# DasAltimeter_V0_2.net
KiCad netlist of a schematic drawn in EAGLE
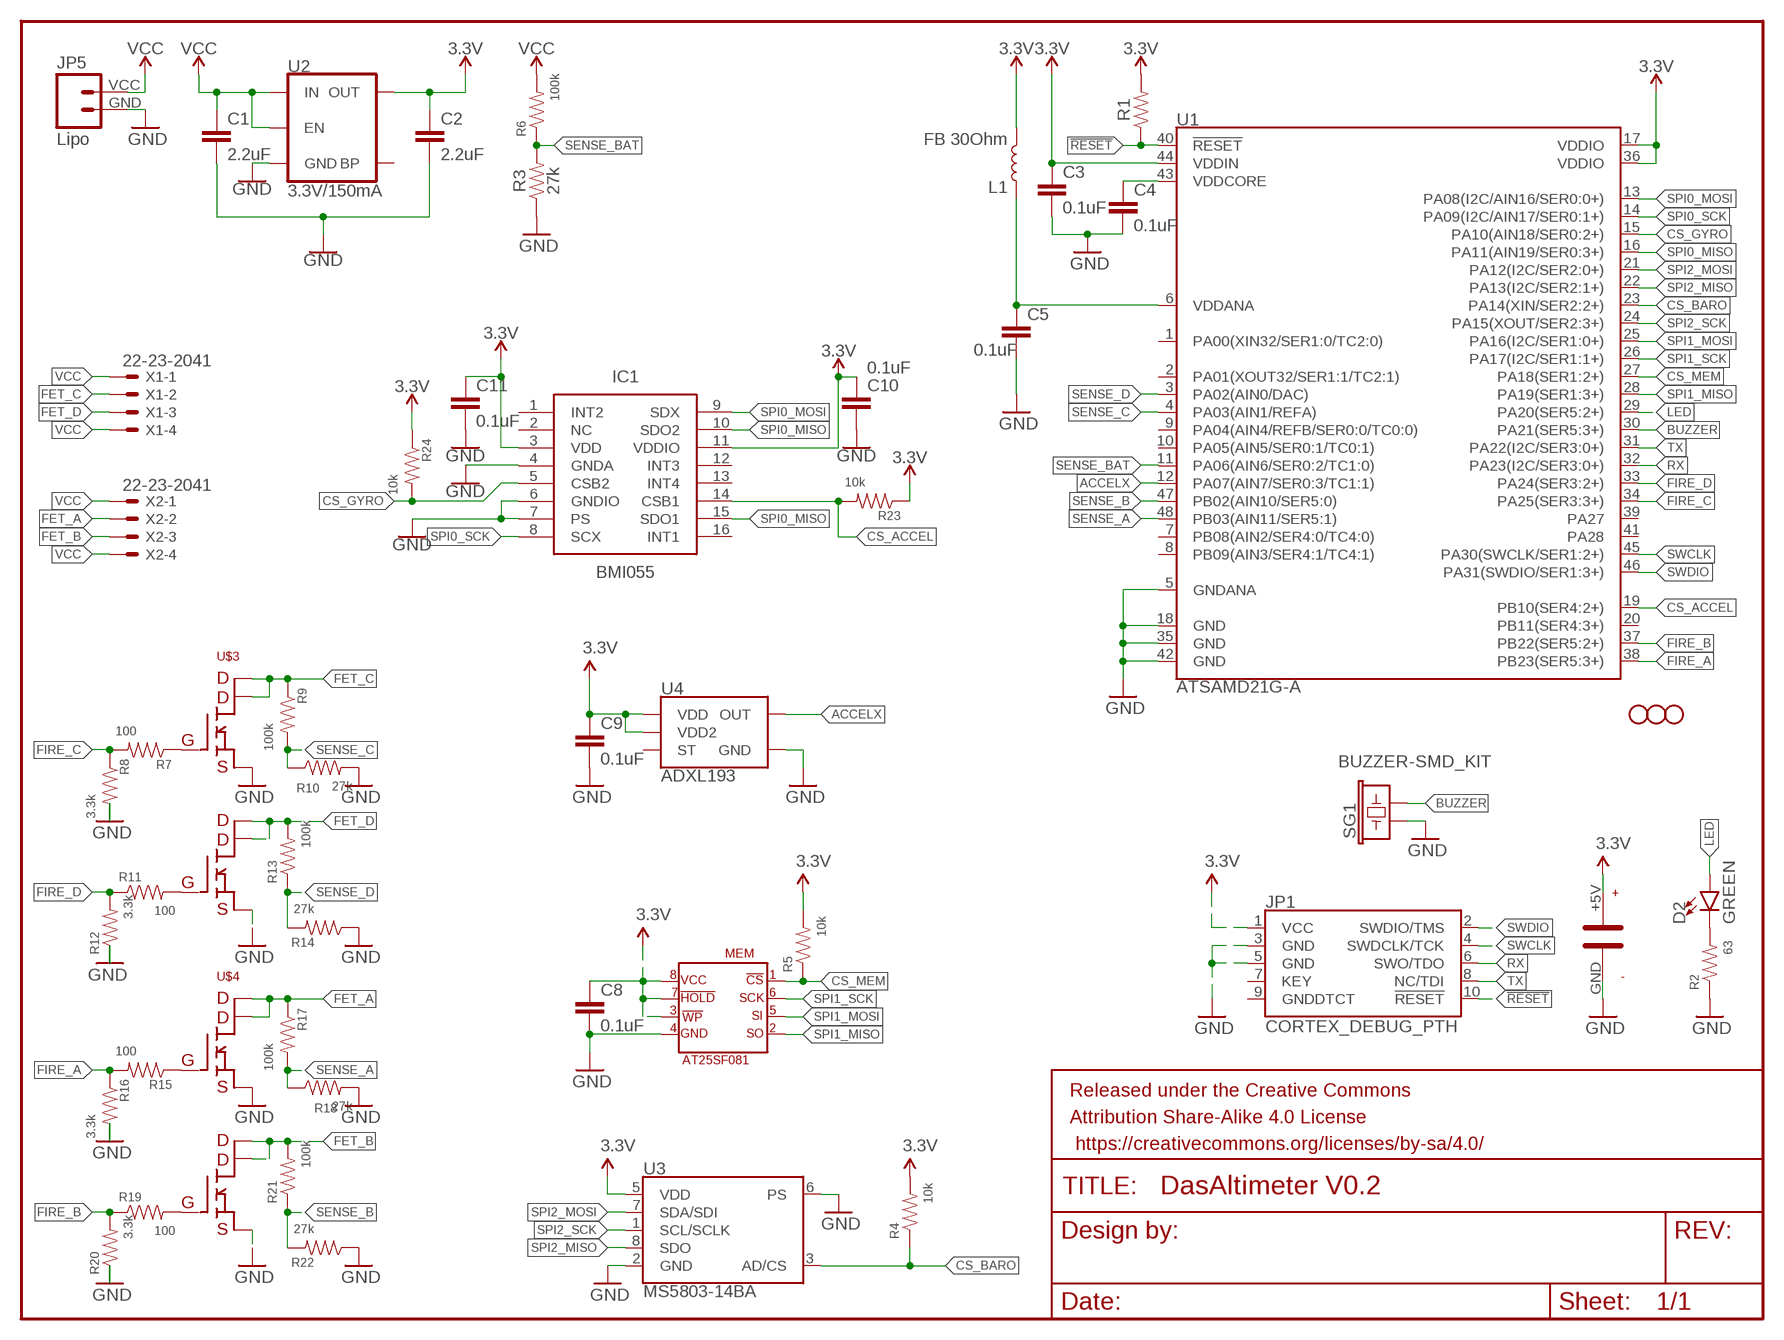
[diagram p0: schematic, sheet 1]

(export (version "E")
  (design (tool "Eeschema 10.0.6"))
  (components
    (comp (ref "C1")
      (value "2.2uF")
      (footprint "eagle-import:0603")
      (libsource (lib "eagle-import") (part "2.2UF-0603-10V-20%"))
    )
    (comp (ref "C2")
      (value "2.2uF")
      (footprint "eagle-import:0603")
      (libsource (lib "eagle-import") (part "2.2UF-0603-10V-20%"))
    )
    (comp (ref "C3")
      (value "0.1uF")
      (footprint "eagle-import:0402")
      (libsource (lib "eagle-import") (part "0.1UF-0402-16V-10%"))
    )
    (comp (ref "C4")
      (value "0.1uF")
      (footprint "eagle-import:0402")
      (libsource (lib "eagle-import") (part "0.1UF-0402-16V-10%"))
    )
    (comp (ref "C5")
      (value "0.1uF")
      (footprint "eagle-import:0402")
      (libsource (lib "eagle-import") (part "0.1UF-0402-16V-10%"))
    )
    (comp (ref "C8")
      (value "0.1uF")
      (footprint "eagle-import:0402")
      (libsource (lib "eagle-import") (part "0.1UF-0402-16V-10%"))
    )
    (comp (ref "C9")
      (value "0.1uF")
      (footprint "eagle-import:0402")
      (libsource (lib "eagle-import") (part "0.1UF-0402-16V-10%"))
    )
    (comp (ref "C10")
      (value "0.1uF")
      (footprint "eagle-import:0402")
      (libsource (lib "eagle-import") (part "0.1UF-0402-16V-10%"))
    )
    (comp (ref "C11")
      (value "0.1uF")
      (footprint "eagle-import:0402")
      (libsource (lib "eagle-import") (part "0.1UF-0402-16V-10%"))
    )
    (comp (ref "D2")
      (value "GREEN")
      (footprint "eagle-import:LED-1206")
      (libsource (lib "eagle-import") (part "LED-GREEN1206"))
    )
    (comp (ref "FRAME1")
      (value "FRAME-LETTERNO_PACKAGE")
      (footprint "eagle-import:DUMMY")
      (fields (field (name "DESIGNER") "Nobody"))
      (libsource (lib "eagle-import") (part "FRAME-LETTERNO_PACKAGE"))
    )
    (comp (ref "H1")
      (value "STAND-OFFTIGHT")
      (footprint "eagle-import:STAND-OFF-TIGHT")
      (libsource (lib "eagle-import") (part "STAND-OFFTIGHT"))
    )
    (comp (ref "H2")
      (value "STAND-OFFTIGHT")
      (footprint "eagle-import:STAND-OFF-TIGHT")
      (libsource (lib "eagle-import") (part "STAND-OFFTIGHT"))
    )
    (comp (ref "H3")
      (value "STAND-OFFTIGHT")
      (footprint "eagle-import:STAND-OFF-TIGHT")
      (libsource (lib "eagle-import") (part "STAND-OFFTIGHT"))
    )
    (comp (ref "IC1")
      (value "BMI055")
      (footprint "eagle-import:BMI055")
      (libsource (lib "eagle-import") (part "BMI055"))
    )
    (comp (ref "JP1")
      (value "CORTEX_DEBUG_PTH")
      (footprint "eagle-import:2X5-PTH-1.27MM")
      (libsource (lib "eagle-import") (part "CORTEX_DEBUG_PTH"))
    )
    (comp (ref "JP5")
      (value "Lipo")
      (footprint "eagle-import:JST-2-SMD-VERT")
      (libsource (lib "eagle-import") (part "M024UCON-15767"))
    )
    (comp (ref "L1")
      (value "FB 30Ohm")
      (footprint "eagle-import:0603")
      (libsource (lib "eagle-import") (part "INDUCTOR-0603-33NH"))
    )
    (comp (ref "MEM")
      (value "AT25SF081")
      (footprint "eagle-import:AT25SF081")
      (libsource (lib "eagle-import") (part "AT25SF081"))
    )
    (comp (ref "R1")
      (value "RESISTOR0402")
      (footprint "eagle-import:0402")
      (libsource (lib "eagle-import") (part "RESISTOR0402"))
    )
    (comp (ref "R2")
      (value "63")
      (footprint "eagle-import:0402")
      (libsource (lib "eagle-import") (part "RESISTOR0402"))
    )
    (comp (ref "R3")
      (value "27k")
      (footprint "eagle-import:0402")
      (libsource (lib "eagle-import") (part "RESISTOR0402"))
    )
    (comp (ref "R4")
      (value "10k")
      (footprint "eagle-import:0402")
      (libsource (lib "eagle-import") (part "RESISTOR0402"))
    )
    (comp (ref "R5")
      (value "10k")
      (footprint "eagle-import:0402")
      (libsource (lib "eagle-import") (part "RESISTOR0402"))
    )
    (comp (ref "R6")
      (value "100k")
      (footprint "eagle-import:0402")
      (libsource (lib "eagle-import") (part "RESISTOR0402"))
    )
    (comp (ref "R7")
      (value "100")
      (footprint "eagle-import:0402")
      (libsource (lib "eagle-import") (part "RESISTOR0402"))
    )
    (comp (ref "R8")
      (value "3.3k")
      (footprint "eagle-import:0402")
      (libsource (lib "eagle-import") (part "RESISTOR0402"))
    )
    (comp (ref "R9")
      (value "100k")
      (footprint "eagle-import:0402")
      (libsource (lib "eagle-import") (part "RESISTOR0402"))
    )
    (comp (ref "R10")
      (value "27k")
      (footprint "eagle-import:0402")
      (libsource (lib "eagle-import") (part "RESISTOR0402"))
    )
    (comp (ref "R11")
      (value "100")
      (footprint "eagle-import:0402")
      (libsource (lib "eagle-import") (part "RESISTOR0402"))
    )
    (comp (ref "R12")
      (value "3.3k")
      (footprint "eagle-import:0402")
      (libsource (lib "eagle-import") (part "RESISTOR0402"))
    )
    (comp (ref "R13")
      (value "100k")
      (footprint "eagle-import:0402")
      (libsource (lib "eagle-import") (part "RESISTOR0402"))
    )
    (comp (ref "R14")
      (value "27k")
      (footprint "eagle-import:0402")
      (libsource (lib "eagle-import") (part "RESISTOR0402"))
    )
    (comp (ref "R15")
      (value "100")
      (footprint "eagle-import:0402")
      (libsource (lib "eagle-import") (part "RESISTOR0402"))
    )
    (comp (ref "R16")
      (value "3.3k")
      (footprint "eagle-import:0402")
      (libsource (lib "eagle-import") (part "RESISTOR0402"))
    )
    (comp (ref "R17")
      (value "100k")
      (footprint "eagle-import:0402")
      (libsource (lib "eagle-import") (part "RESISTOR0402"))
    )
    (comp (ref "R18")
      (value "27k")
      (footprint "eagle-import:0402")
      (libsource (lib "eagle-import") (part "RESISTOR0402"))
    )
    (comp (ref "R19")
      (value "100")
      (footprint "eagle-import:0402")
      (libsource (lib "eagle-import") (part "RESISTOR0402"))
    )
    (comp (ref "R20")
      (value "3.3k")
      (footprint "eagle-import:0402")
      (libsource (lib "eagle-import") (part "RESISTOR0402"))
    )
    (comp (ref "R21")
      (value "100k")
      (footprint "eagle-import:0402")
      (libsource (lib "eagle-import") (part "RESISTOR0402"))
    )
    (comp (ref "R22")
      (value "27k")
      (footprint "eagle-import:0402")
      (libsource (lib "eagle-import") (part "RESISTOR0402"))
    )
    (comp (ref "R23")
      (value "10k")
      (footprint "eagle-import:0402")
      (libsource (lib "eagle-import") (part "RESISTOR0402"))
    )
    (comp (ref "R24")
      (value "10k")
      (footprint "eagle-import:0402")
      (libsource (lib "eagle-import") (part "RESISTOR0402"))
    )
    (comp (ref "SG1")
      (value "BUZZER-SMD_KIT")
      (footprint "eagle-import:BUZZER-CCV-KIT")
      (libsource (lib "eagle-import") (part "BUZZER-SMD_KIT"))
    )
    (comp (ref "U$1")
      (value "PB-5R0H104-R")
      (footprint "eagle-import:PB-5R0H104-R")
      (libsource (lib "eagle-import") (part "PB-5R0H104-R"))
    )
    (comp (ref "U$3")
      (value "SI7232DN")
      (footprint "eagle-import:SI7232DN")
      (libsource (lib "eagle-import") (part "SI7232DN"))
    )
    (comp (ref "U$4")
      (value "SI7232DN")
      (footprint "eagle-import:SI7232DN")
      (libsource (lib "eagle-import") (part "SI7232DN"))
    )
    (comp (ref "U1")
      (value "ATSAMD21G-A")
      (footprint "eagle-import:TQFP-48")
      (libsource (lib "eagle-import") (part "ATSAMD21G-A"))
    )
    (comp (ref "U2")
      (value "3.3V/150mA")
      (footprint "eagle-import:SOT23-5")
      (libsource (lib "eagle-import") (part "V_REG_MIC52053.3V"))
    )
    (comp (ref "U3")
      (value "MS5803-14BA")
      (footprint "eagle-import:MS5803")
      (libsource (lib "eagle-import") (part "MS5803-14BA"))
    )
    (comp (ref "U4")
      (value "ADXL193")
      (footprint "eagle-import:LCC-8")
      (libsource (lib "eagle-import") (part "ADXL193"))
    )
    (comp (ref "X1")
      (value "22-23-2041")
      (footprint "eagle-import:22-23-2041")
      (fields (field (name "MF") "MOLEX"))
      (libsource (lib "eagle-import") (part "22-23-2041"))
    )
    (comp (ref "X2")
      (value "22-23-2041")
      (footprint "eagle-import:22-23-2041")
      (fields (field (name "MF") "MOLEX"))
      (libsource (lib "eagle-import") (part "22-23-2041"))
    )
  )
  (nets
    (net (code "1") (name "/~{RESET}") (class "Default")
      (node (ref "JP1") (pin "10") (pinfunction "~{RESET}_10") (pintype "bidirectional"))
      (node (ref "R1") (pin "1") (pinfunction "1_1") (pintype "passive"))
      (node (ref "U1") (pin "40") (pinfunction "~{RESET}_40") (pintype "bidirectional"))
    )
    (net (code "2") (name "3.3V") (class "Default")
      (node (ref "C10") (pin "1") (pinfunction "1_1") (pintype "passive"))
      (node (ref "C11") (pin "1") (pinfunction "1_1") (pintype "passive"))
      (node (ref "C2") (pin "1") (pinfunction "1_1") (pintype "passive"))
      (node (ref "C3") (pin "1") (pinfunction "1_1") (pintype "passive"))
      (node (ref "C8") (pin "1") (pinfunction "1_1") (pintype "passive"))
      (node (ref "C9") (pin "1") (pinfunction "1_1") (pintype "passive"))
      (node (ref "IC1") (pin "11") (pinfunction "VDDIO_11") (pintype "passive"))
      (node (ref "IC1") (pin "3") (pinfunction "VDD_3") (pintype "passive"))
      (node (ref "JP1") (pin "1") (pinfunction "VCC_1") (pintype "bidirectional"))
      (node (ref "L1") (pin "2") (pinfunction "2_2") (pintype "passive"))
      (node (ref "MEM") (pin "!HOLD") (pinfunction "~{HOLD}_!HOLD") (pintype "bidirectional"))
      (node (ref "MEM") (pin "!WP") (pinfunction "~{WP}_!WP") (pintype "bidirectional"))
      (node (ref "MEM") (pin "VCC") (pinfunction "VCC_VCC") (pintype "bidirectional"))
      (node (ref "R1") (pin "2") (pinfunction "2_2") (pintype "passive"))
      (node (ref "R23") (pin "1") (pinfunction "1_1") (pintype "passive"))
      (node (ref "R24") (pin "1") (pinfunction "1_1") (pintype "passive"))
      (node (ref "R4") (pin "2") (pinfunction "2_2") (pintype "passive"))
      (node (ref "R5") (pin "2") (pinfunction "2_2") (pintype "passive"))
      (node (ref "U$1") (pin "+5V") (pinfunction "+5V_+5V") (pintype "bidirectional"))
      (node (ref "U1") (pin "17") (pinfunction "VDDIO_17") (pintype "bidirectional"))
      (node (ref "U1") (pin "36") (pinfunction "VDDIO_36") (pintype "bidirectional"))
      (node (ref "U1") (pin "44") (pinfunction "VDDIN_44") (pintype "bidirectional"))
      (node (ref "U2") (pin "5") (pinfunction "OUT_5") (pintype "passive"))
      (node (ref "U3") (pin "5") (pinfunction "VDD_5") (pintype "bidirectional"))
      (node (ref "U4") (pin "P$7") (pinfunction "VDD_P$7") (pintype "bidirectional"))
      (node (ref "U4") (pin "P$8") (pinfunction "VDD2_P$8") (pintype "bidirectional"))
    )
    (net (code "3") (name "ACCELX") (class "Default")
      (node (ref "U1") (pin "12") (pinfunction "PA07(AIN7/SER0:3/TC1:1)_12") (pintype "bidirectional"))
      (node (ref "U4") (pin "P$6") (pinfunction "OUT_P$6") (pintype "bidirectional"))
    )
    (net (code "4") (name "BUZZER") (class "Default")
      (node (ref "SG1") (pin "-") (pinfunction "2_-") (pintype "passive"))
      (node (ref "U1") (pin "30") (pinfunction "PA21(SER5:3+)_30") (pintype "bidirectional"))
    )
    (net (code "5") (name "CS_ACCEL") (class "Default")
      (node (ref "IC1") (pin "14") (pinfunction "CSB1_14") (pintype "passive"))
      (node (ref "R23") (pin "2") (pinfunction "2_2") (pintype "passive"))
      (node (ref "U1") (pin "19") (pinfunction "PB10(SER4:2+)_19") (pintype "bidirectional"))
    )
    (net (code "6") (name "CS_BARO") (class "Default")
      (node (ref "R4") (pin "1") (pinfunction "1_1") (pintype "passive"))
      (node (ref "U1") (pin "23") (pinfunction "PA14(XIN/SER2:2+)_23") (pintype "bidirectional"))
      (node (ref "U3") (pin "3") (pinfunction "AD/CS_3") (pintype "bidirectional"))
    )
    (net (code "7") (name "CS_GYRO") (class "Default")
      (node (ref "IC1") (pin "5") (pinfunction "CSB2_5") (pintype "passive"))
      (node (ref "R24") (pin "2") (pinfunction "2_2") (pintype "passive"))
      (node (ref "U1") (pin "15") (pinfunction "PA10(AIN18/SER0:2+)_15") (pintype "bidirectional"))
    )
    (net (code "8") (name "CS_MEM") (class "Default")
      (node (ref "MEM") (pin "!CS") (pinfunction "~{CS}_!CS") (pintype "bidirectional"))
      (node (ref "R5") (pin "1") (pinfunction "1_1") (pintype "passive"))
      (node (ref "U1") (pin "27") (pinfunction "PA18(SER1:2+)_27") (pintype "bidirectional"))
    )
    (net (code "9") (name "FET_A") (class "Default")
      (node (ref "R17") (pin "1") (pinfunction "1_1") (pintype "passive"))
      (node (ref "U$4") (pin "7") (pinfunction "PIN7_7") (pintype "bidirectional"))
      (node (ref "U$4") (pin "8") (pinfunction "PIN8_8") (pintype "bidirectional"))
      (node (ref "U$4") (pin "9") (pinfunction "PIN8_9") (pintype "bidirectional"))
      (node (ref "X2") (pin "2") (pinfunction "S_2") (pintype "passive"))
    )
    (net (code "10") (name "FET_B") (class "Default")
      (node (ref "R21") (pin "2") (pinfunction "2_2") (pintype "passive"))
      (node (ref "U$4") (pin "10") (pinfunction "PIN5_10") (pintype "bidirectional"))
      (node (ref "U$4") (pin "5") (pinfunction "PIN5_5") (pintype "bidirectional"))
      (node (ref "U$4") (pin "6") (pinfunction "PIN6_6") (pintype "bidirectional"))
      (node (ref "X2") (pin "3") (pinfunction "S_3") (pintype "passive"))
    )
    (net (code "11") (name "FET_C") (class "Default")
      (node (ref "R9") (pin "1") (pinfunction "1_1") (pintype "passive"))
      (node (ref "U$3") (pin "7") (pinfunction "PIN7_7") (pintype "bidirectional"))
      (node (ref "U$3") (pin "8") (pinfunction "PIN8_8") (pintype "bidirectional"))
      (node (ref "U$3") (pin "9") (pinfunction "PIN8_9") (pintype "bidirectional"))
      (node (ref "X1") (pin "2") (pinfunction "S_2") (pintype "passive"))
    )
    (net (code "12") (name "FET_D") (class "Default")
      (node (ref "R13") (pin "2") (pinfunction "2_2") (pintype "passive"))
      (node (ref "U$3") (pin "10") (pinfunction "PIN5_10") (pintype "bidirectional"))
      (node (ref "U$3") (pin "5") (pinfunction "PIN5_5") (pintype "bidirectional"))
      (node (ref "U$3") (pin "6") (pinfunction "PIN6_6") (pintype "bidirectional"))
      (node (ref "X1") (pin "3") (pinfunction "S_3") (pintype "passive"))
    )
    (net (code "13") (name "FIRE_A") (class "Default")
      (node (ref "R15") (pin "2") (pinfunction "2_2") (pintype "passive"))
      (node (ref "R16") (pin "1") (pinfunction "1_1") (pintype "passive"))
      (node (ref "U1") (pin "38") (pinfunction "PB23(SER5:3+)_38") (pintype "bidirectional"))
    )
    (net (code "14") (name "FIRE_B") (class "Default")
      (node (ref "R19") (pin "1") (pinfunction "1_1") (pintype "passive"))
      (node (ref "R20") (pin "2") (pinfunction "2_2") (pintype "passive"))
      (node (ref "U1") (pin "37") (pinfunction "PB22(SER5:2+)_37") (pintype "bidirectional"))
    )
    (net (code "15") (name "FIRE_C") (class "Default")
      (node (ref "R7") (pin "2") (pinfunction "2_2") (pintype "passive"))
      (node (ref "R8") (pin "1") (pinfunction "1_1") (pintype "passive"))
      (node (ref "U1") (pin "34") (pinfunction "PA25(SER3:3+)_34") (pintype "bidirectional"))
    )
    (net (code "16") (name "FIRE_D") (class "Default")
      (node (ref "R11") (pin "1") (pinfunction "1_1") (pintype "passive"))
      (node (ref "R12") (pin "2") (pinfunction "2_2") (pintype "passive"))
      (node (ref "U1") (pin "33") (pinfunction "PA24(SER3:2+)_33") (pintype "bidirectional"))
    )
    (net (code "17") (name "GND") (class "Default")
      (node (ref "C1") (pin "2") (pinfunction "2_2") (pintype "passive"))
      (node (ref "C10") (pin "2") (pinfunction "2_2") (pintype "passive"))
      (node (ref "C11") (pin "2") (pinfunction "2_2") (pintype "passive"))
      (node (ref "C2") (pin "2") (pinfunction "2_2") (pintype "passive"))
      (node (ref "C3") (pin "2") (pinfunction "2_2") (pintype "passive"))
      (node (ref "C4") (pin "2") (pinfunction "2_2") (pintype "passive"))
      (node (ref "C5") (pin "2") (pinfunction "2_2") (pintype "passive"))
      (node (ref "C8") (pin "2") (pinfunction "2_2") (pintype "passive"))
      (node (ref "C9") (pin "2") (pinfunction "2_2") (pintype "passive"))
      (node (ref "IC1") (pin "4") (pinfunction "GNDA_4") (pintype "passive"))
      (node (ref "IC1") (pin "6") (pinfunction "GNDIO_6") (pintype "passive"))
      (node (ref "IC1") (pin "7") (pinfunction "PS_7") (pintype "passive"))
      (node (ref "JP1") (pin "3") (pinfunction "GND_3") (pintype "bidirectional"))
      (node (ref "JP1") (pin "5") (pinfunction "GND_5") (pintype "bidirectional"))
      (node (ref "JP5") (pin "GND") (pinfunction "1_GND") (pintype "passive"))
      (node (ref "MEM") (pin "GND") (pinfunction "GND_GND") (pintype "bidirectional"))
      (node (ref "R10") (pin "2") (pinfunction "2_2") (pintype "passive"))
      (node (ref "R12") (pin "1") (pinfunction "1_1") (pintype "passive"))
      (node (ref "R14") (pin "1") (pinfunction "1_1") (pintype "passive"))
      (node (ref "R16") (pin "2") (pinfunction "2_2") (pintype "passive"))
      (node (ref "R18") (pin "2") (pinfunction "2_2") (pintype "passive"))
      (node (ref "R2") (pin "1") (pinfunction "1_1") (pintype "passive"))
      (node (ref "R20") (pin "1") (pinfunction "1_1") (pintype "passive"))
      (node (ref "R22") (pin "1") (pinfunction "1_1") (pintype "passive"))
      (node (ref "R3") (pin "1") (pinfunction "1_1") (pintype "passive"))
      (node (ref "R8") (pin "2") (pinfunction "2_2") (pintype "passive"))
      (node (ref "SG1") (pin "+") (pinfunction "1_+") (pintype "passive"))
      (node (ref "U$1") (pin "GND") (pinfunction "GND_GND") (pintype "bidirectional"))
      (node (ref "U$3") (pin "1") (pinfunction "PIN1_1") (pintype "bidirectional"))
      (node (ref "U$3") (pin "3") (pinfunction "PIN3_3") (pintype "bidirectional"))
      (node (ref "U$4") (pin "1") (pinfunction "PIN1_1") (pintype "bidirectional"))
      (node (ref "U$4") (pin "3") (pinfunction "PIN3_3") (pintype "bidirectional"))
      (node (ref "U1") (pin "18") (pinfunction "GND_18") (pintype "bidirectional"))
      (node (ref "U1") (pin "35") (pinfunction "GND_35") (pintype "bidirectional"))
      (node (ref "U1") (pin "42") (pinfunction "GND_42") (pintype "bidirectional"))
      (node (ref "U1") (pin "5") (pinfunction "GNDANA_5") (pintype "bidirectional"))
      (node (ref "U2") (pin "2") (pinfunction "GND_2") (pintype "input"))
      (node (ref "U3") (pin "2") (pinfunction "GND_2") (pintype "bidirectional"))
      (node (ref "U3") (pin "6") (pinfunction "PS_6") (pintype "bidirectional"))
      (node (ref "U4") (pin "P$3") (pinfunction "GND_P$3") (pintype "bidirectional"))
    )
    (net (code "18") (name "LED") (class "Default")
      (node (ref "D2") (pin "A") (pinfunction "A_A") (pintype "passive"))
      (node (ref "U1") (pin "29") (pinfunction "PA20(SER5:2+)_29") (pintype "bidirectional"))
    )
    (net (code "19") (name "Net-(D2-PadC)") (class "Default")
      (node (ref "D2") (pin "C") (pinfunction "C_C") (pintype "passive"))
      (node (ref "R2") (pin "2") (pinfunction "2_2") (pintype "passive"))
    )
    (net (code "20") (name "Net-(U$3-PIN2)") (class "Default")
      (node (ref "R7") (pin "1") (pinfunction "1_1") (pintype "passive"))
      (node (ref "U$3") (pin "2") (pinfunction "PIN2_2") (pintype "bidirectional"))
    )
    (net (code "21") (name "Net-(U$3-PIN4)") (class "Default")
      (node (ref "R11") (pin "2") (pinfunction "2_2") (pintype "passive"))
      (node (ref "U$3") (pin "4") (pinfunction "PIN4_4") (pintype "bidirectional"))
    )
    (net (code "22") (name "Net-(U$4-PIN2)") (class "Default")
      (node (ref "R15") (pin "1") (pinfunction "1_1") (pintype "passive"))
      (node (ref "U$4") (pin "2") (pinfunction "PIN2_2") (pintype "bidirectional"))
    )
    (net (code "23") (name "Net-(U$4-PIN4)") (class "Default")
      (node (ref "R19") (pin "2") (pinfunction "2_2") (pintype "passive"))
      (node (ref "U$4") (pin "4") (pinfunction "PIN4_4") (pintype "bidirectional"))
    )
    (net (code "24") (name "Net-(U1-VDDANA)") (class "Default")
      (node (ref "C5") (pin "1") (pinfunction "1_1") (pintype "passive"))
      (node (ref "L1") (pin "1") (pinfunction "1_1") (pintype "passive"))
      (node (ref "U1") (pin "6") (pinfunction "VDDANA_6") (pintype "bidirectional"))
    )
    (net (code "25") (name "Net-(U1-VDDCORE)") (class "Default")
      (node (ref "C4") (pin "1") (pinfunction "1_1") (pintype "passive"))
      (node (ref "U1") (pin "43") (pinfunction "VDDCORE_43") (pintype "bidirectional"))
    )
    (net (code "26") (name "RX") (class "Default")
      (node (ref "JP1") (pin "6") (pinfunction "SWO/TDO_6") (pintype "bidirectional"))
      (node (ref "U1") (pin "32") (pinfunction "PA23(I2C/SER3:0+)_32") (pintype "bidirectional"))
    )
    (net (code "27") (name "SENSE_A") (class "Default")
      (node (ref "R17") (pin "2") (pinfunction "2_2") (pintype "passive"))
      (node (ref "R18") (pin "1") (pinfunction "1_1") (pintype "passive"))
      (node (ref "U1") (pin "48") (pinfunction "PB03(AIN11/SER5:1)_48") (pintype "bidirectional"))
    )
    (net (code "28") (name "SENSE_B") (class "Default")
      (node (ref "R21") (pin "1") (pinfunction "1_1") (pintype "passive"))
      (node (ref "R22") (pin "2") (pinfunction "2_2") (pintype "passive"))
      (node (ref "U1") (pin "47") (pinfunction "PB02(AIN10/SER5:0)_47") (pintype "bidirectional"))
    )
    (net (code "29") (name "SENSE_BAT") (class "Default")
      (node (ref "R3") (pin "2") (pinfunction "2_2") (pintype "passive"))
      (node (ref "R6") (pin "1") (pinfunction "1_1") (pintype "passive"))
      (node (ref "U1") (pin "11") (pinfunction "PA06(AIN6/SER0:2/TC1:0)_11") (pintype "bidirectional"))
    )
    (net (code "30") (name "SENSE_C") (class "Default")
      (node (ref "R10") (pin "1") (pinfunction "1_1") (pintype "passive"))
      (node (ref "R9") (pin "2") (pinfunction "2_2") (pintype "passive"))
      (node (ref "U1") (pin "4") (pinfunction "PA03(AIN1/REFA)_4") (pintype "bidirectional"))
    )
    (net (code "31") (name "SENSE_D") (class "Default")
      (node (ref "R13") (pin "1") (pinfunction "1_1") (pintype "passive"))
      (node (ref "R14") (pin "2") (pinfunction "2_2") (pintype "passive"))
      (node (ref "U1") (pin "3") (pinfunction "PA02(AIN0/DAC)_3") (pintype "bidirectional"))
    )
    (net (code "32") (name "SPI0_MISO") (class "Default")
      (node (ref "IC1") (pin "10") (pinfunction "SDO2_10") (pintype "passive"))
      (node (ref "IC1") (pin "15") (pinfunction "SDO1_15") (pintype "passive"))
      (node (ref "U1") (pin "16") (pinfunction "PA11(AIN19/SER0:3+)_16") (pintype "bidirectional"))
    )
    (net (code "33") (name "SPI0_MOSI") (class "Default")
      (node (ref "IC1") (pin "9") (pinfunction "SDX_9") (pintype "passive"))
      (node (ref "U1") (pin "13") (pinfunction "PA08(I2C/AIN16/SER0:0+)_13") (pintype "bidirectional"))
    )
    (net (code "34") (name "SPI0_SCK") (class "Default")
      (node (ref "IC1") (pin "8") (pinfunction "SCX_8") (pintype "passive"))
      (node (ref "U1") (pin "14") (pinfunction "PA09(I2C/AIN17/SER0:1+)_14") (pintype "bidirectional"))
    )
    (net (code "35") (name "SPI1_MISO") (class "Default")
      (node (ref "MEM") (pin "SO") (pinfunction "SO_SO") (pintype "bidirectional"))
      (node (ref "U1") (pin "28") (pinfunction "PA19(SER1:3+)_28") (pintype "bidirectional"))
    )
    (net (code "36") (name "SPI1_MOSI") (class "Default")
      (node (ref "MEM") (pin "SI") (pinfunction "SI_SI") (pintype "bidirectional"))
      (node (ref "U1") (pin "25") (pinfunction "PA16(I2C/SER1:0+)_25") (pintype "bidirectional"))
    )
    (net (code "37") (name "SPI1_SCK") (class "Default")
      (node (ref "MEM") (pin "SCK") (pinfunction "SCK_SCK") (pintype "bidirectional"))
      (node (ref "U1") (pin "26") (pinfunction "PA17(I2C/SER1:1+)_26") (pintype "bidirectional"))
    )
    (net (code "38") (name "SPI2_MISO") (class "Default")
      (node (ref "U1") (pin "22") (pinfunction "PA13(I2C/SER2:1+)_22") (pintype "bidirectional"))
      (node (ref "U3") (pin "8") (pinfunction "SDO_8") (pintype "bidirectional"))
    )
    (net (code "39") (name "SPI2_MOSI") (class "Default")
      (node (ref "U1") (pin "21") (pinfunction "PA12(I2C/SER2:0+)_21") (pintype "bidirectional"))
      (node (ref "U3") (pin "7") (pinfunction "SDA/SDI_7") (pintype "bidirectional"))
    )
    (net (code "40") (name "SPI2_SCK") (class "Default")
      (node (ref "U1") (pin "24") (pinfunction "PA15(XOUT/SER2:3+)_24") (pintype "bidirectional"))
      (node (ref "U3") (pin "1") (pinfunction "SCL/SCLK_1") (pintype "bidirectional"))
    )
    (net (code "41") (name "SWCLK") (class "Default")
      (node (ref "JP1") (pin "4") (pinfunction "SWDCLK/TCK_4") (pintype "bidirectional"))
      (node (ref "U1") (pin "45") (pinfunction "PA30(SWCLK/SER1:2+)_45") (pintype "bidirectional"))
    )
    (net (code "42") (name "SWDIO") (class "Default")
      (node (ref "JP1") (pin "2") (pinfunction "SWDIO/TMS_2") (pintype "bidirectional"))
      (node (ref "U1") (pin "46") (pinfunction "PA31(SWDIO/SER1:3+)_46") (pintype "bidirectional"))
    )
    (net (code "43") (name "TX") (class "Default")
      (node (ref "JP1") (pin "8") (pinfunction "NC/TDI_8") (pintype "bidirectional"))
      (node (ref "U1") (pin "31") (pinfunction "PA22(I2C/SER3:0+)_31") (pintype "bidirectional"))
    )
    (net (code "44") (name "VCC") (class "Default")
      (node (ref "C1") (pin "1") (pinfunction "1_1") (pintype "passive"))
      (node (ref "JP5") (pin "VCC") (pinfunction "2_VCC") (pintype "passive"))
      (node (ref "R6") (pin "2") (pinfunction "2_2") (pintype "passive"))
      (node (ref "U2") (pin "1") (pinfunction "IN_1") (pintype "input"))
      (node (ref "U2") (pin "3") (pinfunction "EN_3") (pintype "input"))
      (node (ref "X1") (pin "1") (pinfunction "S_1") (pintype "passive"))
      (node (ref "X1") (pin "4") (pinfunction "S_4") (pintype "passive"))
      (node (ref "X2") (pin "1") (pinfunction "S_1") (pintype "passive"))
      (node (ref "X2") (pin "4") (pinfunction "S_4") (pintype "passive"))
    )
    (net (code "45") (name "unconnected-(IC1-INT1-Pad16)") (class "Default")
      (node (ref "IC1") (pin "16") (pinfunction "INT1_16") (pintype "passive"))
    )
    (net (code "46") (name "unconnected-(IC1-INT2-Pad1)") (class "Default")
      (node (ref "IC1") (pin "1") (pinfunction "INT2_1") (pintype "passive"))
    )
    (net (code "47") (name "unconnected-(IC1-INT3-Pad12)") (class "Default")
      (node (ref "IC1") (pin "12") (pinfunction "INT3_12") (pintype "passive"))
    )
    (net (code "48") (name "unconnected-(IC1-INT4-Pad13)") (class "Default")
      (node (ref "IC1") (pin "13") (pinfunction "INT4_13") (pintype "passive"))
    )
    (net (code "49") (name "unconnected-(IC1-NC-Pad2)") (class "Default")
      (node (ref "IC1") (pin "2") (pinfunction "NC_2") (pintype "no_connect"))
    )
    (net (code "50") (name "unconnected-(JP1-GNDDTCT-Pad9)") (class "Default")
      (node (ref "JP1") (pin "9") (pinfunction "GNDDTCT_9") (pintype "bidirectional"))
    )
    (net (code "51") (name "unconnected-(JP1-KEY-Pad7)") (class "Default")
      (node (ref "JP1") (pin "7") (pinfunction "KEY_7") (pintype "bidirectional"))
    )
    (net (code "52") (name "unconnected-(U1-PA00(XIN32{slash}SER1:0{slash}TC2:0)-Pad1)") (class "Default")
      (node (ref "U1") (pin "1") (pinfunction "PA00(XIN32/SER1:0/TC2:0)_1") (pintype "bidirectional"))
    )
    (net (code "53") (name "unconnected-(U1-PA01(XOUT32{slash}SER1:1{slash}TC2:1)-Pad2)") (class "Default")
      (node (ref "U1") (pin "2") (pinfunction "PA01(XOUT32/SER1:1/TC2:1)_2") (pintype "bidirectional"))
    )
    (net (code "54") (name "unconnected-(U1-PA04(AIN4{slash}REFB{slash}SER0:0{slash}TC0:0)-Pad9)") (class "Default")
      (node (ref "U1") (pin "9") (pinfunction "PA04(AIN4/REFB/SER0:0/TC0:0)_9") (pintype "bidirectional"))
    )
    (net (code "55") (name "unconnected-(U1-PA05(AIN5{slash}SER0:1{slash}TC0:1)-Pad10)") (class "Default")
      (node (ref "U1") (pin "10") (pinfunction "PA05(AIN5/SER0:1/TC0:1)_10") (pintype "bidirectional"))
    )
    (net (code "56") (name "unconnected-(U1-PA27-Pad39)") (class "Default")
      (node (ref "U1") (pin "39") (pinfunction "PA27_39") (pintype "bidirectional"))
    )
    (net (code "57") (name "unconnected-(U1-PA28-Pad41)") (class "Default")
      (node (ref "U1") (pin "41") (pinfunction "PA28_41") (pintype "bidirectional"))
    )
    (net (code "58") (name "unconnected-(U1-PB08(AIN2{slash}SER4:0{slash}TC4:0)-Pad7)") (class "Default")
      (node (ref "U1") (pin "7") (pinfunction "PB08(AIN2/SER4:0/TC4:0)_7") (pintype "bidirectional"))
    )
    (net (code "59") (name "unconnected-(U1-PB09(AIN3{slash}SER4:1{slash}TC4:1)-Pad8)") (class "Default")
      (node (ref "U1") (pin "8") (pinfunction "PB09(AIN3/SER4:1/TC4:1)_8") (pintype "bidirectional"))
    )
    (net (code "60") (name "unconnected-(U1-PB11(SER4:3+)-Pad20)") (class "Default")
      (node (ref "U1") (pin "20") (pinfunction "PB11(SER4:3+)_20") (pintype "bidirectional"))
    )
    (net (code "61") (name "unconnected-(U2-BP-Pad4)") (class "Default")
      (node (ref "U2") (pin "4") (pinfunction "BP_4") (pintype "input"))
    )
    (net (code "62") (name "unconnected-(U4-ST-PadP$4)") (class "Default")
      (node (ref "U4") (pin "P$4") (pinfunction "ST_P$4") (pintype "bidirectional"))
    )
  )
)
